# 14_Clocks_1.net
KiCad netlist of a schematic drawn in Altium Designer
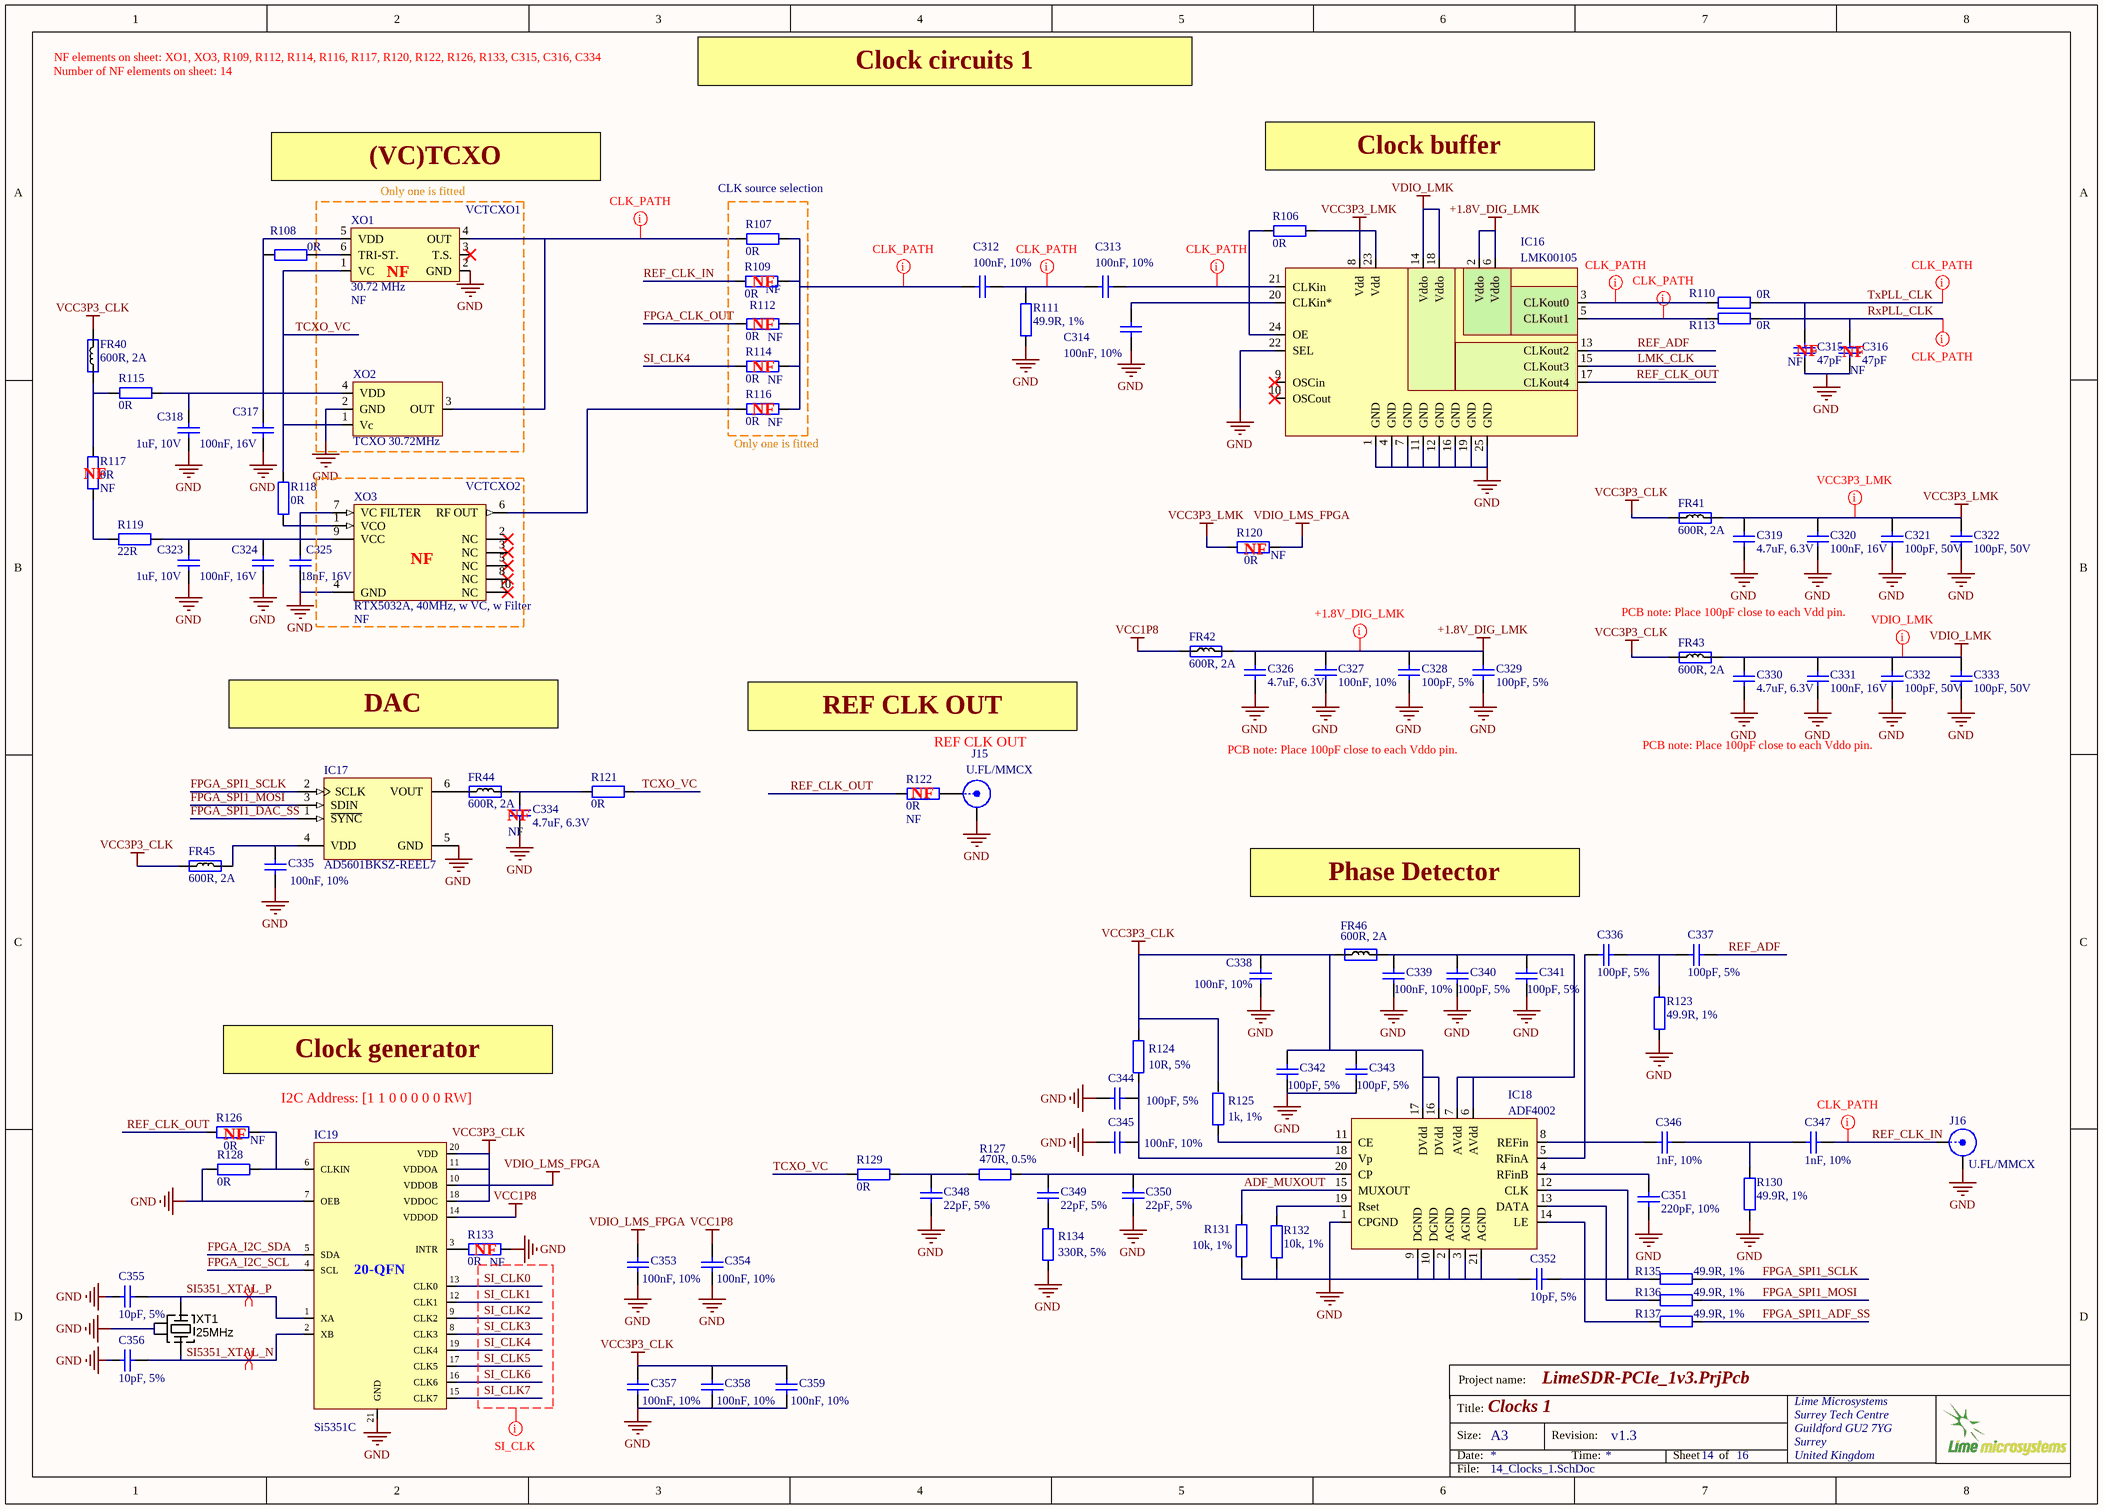
[diagram p0: 14_Clocks_1.SchDoc]

(export (version "E")
  (design (tool "Eeschema 10.0.6"))
  (components
    (comp (ref "C312")
      (value "100nF, 10%")
      (footprint "CAP0402")
      (fields
        (field (name "MANUFACTURER") "Murata Electronics")
        (field (name "TOLERANCE") "10 %")
        (field (name "MANUFACTURER PART NUMBER") "GRM155R71C104KA88D")
      )
      (libsource (lib "LimeMicroAltiumLib_schLib") (part "Cap_0402"))
    )
    (comp (ref "C313")
      (value "100nF, 10%")
      (footprint "CAP0402")
      (fields
        (field (name "MANUFACTURER") "Murata Electronics")
        (field (name "TOLERANCE") "10 %")
        (field (name "MANUFACTURER PART NUMBER") "GRM155R71C104KA88D")
      )
      (libsource (lib "LimeMicroAltiumLib_schLib") (part "Cap_0402"))
    )
    (comp (ref "C314")
      (value "100nF, 10%")
      (footprint "CAP0402")
      (fields
        (field (name "MANUFACTURER") "Murata Electronics")
        (field (name "TOLERANCE") "10 %")
        (field (name "MANUFACTURER PART NUMBER") "GRM155R71C104KA88D")
      )
      (libsource (lib "LimeMicroAltiumLib_schLib") (part "Cap_0402"))
    )
    (comp (ref "C315")
      (value "47pF")
      (footprint "CAP0402")
      (fields
        (field (name "TOLERANCE") "±1%")
        (field (name "MANUFACTURER") "TDK Corporation")
        (field (name "ASSEMBLY INFO") "NF")
      )
      (libsource (lib "LimeMicroAltiumLib_schLib") (part "Cap_0402"))
    )
    (comp (ref "C316")
      (value "47pF")
      (footprint "CAP0402")
      (fields
        (field (name "TOLERANCE") "±1%")
        (field (name "MANUFACTURER") "TDK Corporation")
        (field (name "ASSEMBLY INFO") "NF")
      )
      (libsource (lib "LimeMicroAltiumLib_schLib") (part "Cap_0402"))
    )
    (comp (ref "C317")
      (value "100nF, 16V")
      (footprint "CAP0402")
      (fields
        (field (name "MANUFACTURER") "Murata Electronics")
        (field (name "TOLERANCE") "10 %")
        (field (name "MANUFACTURER PART NUMBER") "GRM155R71C104KA88D")
      )
      (libsource (lib "LimeMicroAltiumLib_schLib") (part "Cap_0402"))
    )
    (comp (ref "C318")
      (value "1uF, 10V")
      (footprint "CAP0402")
      (fields (field (name "MANUFACTURER") "TDK"))
      (libsource (lib "LimeMicroAltiumLib_schLib") (part "Cap_0402"))
    )
    (comp (ref "C319")
      (value "4.7uF, 6.3V")
      (footprint "CAP0402")
      (fields
        (field (name "MANUFACTURER") "Murata Electronics North America")
        (field (name "TOLERANCE") "±20%")
      )
      (libsource (lib "LimeMicroAltiumLib_schLib") (part "Cap_0402"))
    )
    (comp (ref "C320")
      (value "100nF, 16V")
      (footprint "CAP0402")
      (fields
        (field (name "MANUFACTURER") "Murata Electronics")
        (field (name "TOLERANCE") "10 %")
        (field (name "MANUFACTURER PART NUMBER") "GRM155R71C104KA88D")
      )
      (libsource (lib "LimeMicroAltiumLib_schLib") (part "Cap_0402"))
    )
    (comp (ref "C321")
      (value "100pF, 50V")
      (footprint "CAP0402")
      (fields (field (name "MANUFACTURER") "Yageo") (field (name "TOLERANCE") "±5%"))
      (libsource (lib "LimeMicroAltiumLib_schLib") (part "Cap_0402"))
    )
    (comp (ref "C322")
      (value "100pF, 50V")
      (footprint "CAP0402")
      (fields (field (name "MANUFACTURER") "Yageo") (field (name "TOLERANCE") "±5%"))
      (libsource (lib "LimeMicroAltiumLib_schLib") (part "Cap_0402"))
    )
    (comp (ref "C323")
      (value "1uF, 10V")
      (footprint "CAP0402")
      (fields (field (name "MANUFACTURER") "TDK"))
      (libsource (lib "LimeMicroAltiumLib_schLib") (part "Cap_0402"))
    )
    (comp (ref "C324")
      (value "100nF, 16V")
      (footprint "CAP0402")
      (fields
        (field (name "MANUFACTURER") "Murata Electronics")
        (field (name "TOLERANCE") "10 %")
        (field (name "MANUFACTURER PART NUMBER") "GRM155R71C104KA88D")
      )
      (libsource (lib "LimeMicroAltiumLib_schLib") (part "Cap_0402"))
    )
    (comp (ref "C325")
      (value "18nF, 16V")
      (footprint "CAP0402")
      (fields (field (name "MANUFACTURER") "Yageo") (field (name "TOLERANCE") "±10%"))
      (libsource (lib "LimeMicroAltiumLib_schLib") (part "Cap_0402"))
    )
    (comp (ref "C326")
      (value "4.7uF, 6.3V")
      (footprint "CAP0402")
      (fields
        (field (name "MANUFACTURER") "Murata Electronics North America")
        (field (name "TOLERANCE") "±20%")
      )
      (libsource (lib "LimeMicroAltiumLib_schLib") (part "Cap_0402"))
    )
    (comp (ref "C327")
      (value "100nF, 10%")
      (footprint "CAP0402")
      (fields
        (field (name "MANUFACTURER") "Murata Electronics")
        (field (name "TOLERANCE") "10 %")
        (field (name "MANUFACTURER PART NUMBER") "GRM155R71C104KA88D")
      )
      (libsource (lib "LimeMicroAltiumLib_schLib") (part "Cap_0402"))
    )
    (comp (ref "C328")
      (value "100pF, 5%")
      (footprint "CAP0402")
      (fields (field (name "MANUFACTURER") "Yageo") (field (name "TOLERANCE") "±5%"))
      (libsource (lib "LimeMicroAltiumLib_schLib") (part "Cap_0402"))
    )
    (comp (ref "C329")
      (value "100pF, 5%")
      (footprint "CAP0402")
      (fields (field (name "MANUFACTURER") "Yageo") (field (name "TOLERANCE") "±5%"))
      (libsource (lib "LimeMicroAltiumLib_schLib") (part "Cap_0402"))
    )
    (comp (ref "C330")
      (value "4.7uF, 6.3V")
      (footprint "CAP0402")
      (fields
        (field (name "MANUFACTURER") "Murata Electronics North America")
        (field (name "TOLERANCE") "±20%")
      )
      (libsource (lib "LimeMicroAltiumLib_schLib") (part "Cap_0402"))
    )
    (comp (ref "C331")
      (value "100nF, 16V")
      (footprint "CAP0402")
      (fields
        (field (name "MANUFACTURER") "Murata Electronics")
        (field (name "TOLERANCE") "10 %")
        (field (name "MANUFACTURER PART NUMBER") "GRM155R71C104KA88D")
      )
      (libsource (lib "LimeMicroAltiumLib_schLib") (part "Cap_0402"))
    )
    (comp (ref "C332")
      (value "100pF, 50V")
      (footprint "CAP0402")
      (fields (field (name "MANUFACTURER") "Yageo") (field (name "TOLERANCE") "±5%"))
      (libsource (lib "LimeMicroAltiumLib_schLib") (part "Cap_0402"))
    )
    (comp (ref "C333")
      (value "100pF, 50V")
      (footprint "CAP0402")
      (fields (field (name "MANUFACTURER") "Yageo") (field (name "TOLERANCE") "±5%"))
      (libsource (lib "LimeMicroAltiumLib_schLib") (part "Cap_0402"))
    )
    (comp (ref "C334")
      (value "4.7uF, 6.3V")
      (footprint "CAP0402")
      (fields
        (field (name "ASSEMBLY INFO") "NF")
        (field (name "MANUFACTURER") "Murata Electronics North America")
        (field (name "TOLERANCE") "±20%")
      )
      (libsource (lib "LimeMicroAltiumLib_schLib") (part "Cap_0402"))
    )
    (comp (ref "C335")
      (value "100nF, 10%")
      (footprint "CAP0402")
      (fields
        (field (name "TOLERANCE") "10 %")
        (field (name "MANUFACTURER") "Murata Electronics")
        (field (name "MANUFACTURER PART NUMBER") "GRM155R71C104KA88D")
      )
      (libsource (lib "LimeFPGAboard_schLib") (part "Cap_0603"))
    )
    (comp (ref "C336")
      (value "100pF, 5%")
      (footprint "CAP0402")
      (fields (field (name "MANUFACTURER") "Yageo") (field (name "TOLERANCE") "±5%"))
      (libsource (lib "LimeMicroAltiumLib_schLib") (part "Cap_0402"))
    )
    (comp (ref "C337")
      (value "100pF, 5%")
      (footprint "CAP0402")
      (fields (field (name "MANUFACTURER") "Yageo") (field (name "TOLERANCE") "±5%"))
      (libsource (lib "LimeMicroAltiumLib_schLib") (part "Cap_0402"))
    )
    (comp (ref "C338")
      (value "100nF, 10%")
      (footprint "CAP0402")
      (fields
        (field (name "MANUFACTURER") "Murata Electronics")
        (field (name "TOLERANCE") "10 %")
        (field (name "MANUFACTURER PART NUMBER") "GRM155R71C104KA88D")
      )
      (libsource (lib "LimeMicroAltiumLib_schLib") (part "Cap_0402"))
    )
    (comp (ref "C339")
      (value "100nF, 10%")
      (footprint "CAP0402")
      (fields
        (field (name "MANUFACTURER") "Murata Electronics")
        (field (name "TOLERANCE") "10 %")
        (field (name "MANUFACTURER PART NUMBER") "GRM155R71C104KA88D")
      )
      (libsource (lib "LimeMicroAltiumLib_schLib") (part "Cap_0402"))
    )
    (comp (ref "C340")
      (value "100pF, 5%")
      (footprint "CAP0402")
      (fields (field (name "MANUFACTURER") "Yageo") (field (name "TOLERANCE") "±5%"))
      (libsource (lib "LimeMicroAltiumLib_schLib") (part "Cap_0402"))
    )
    (comp (ref "C341")
      (value "100pF, 5%")
      (footprint "CAP0402")
      (fields (field (name "MANUFACTURER") "Yageo") (field (name "TOLERANCE") "±5%"))
      (libsource (lib "LimeMicroAltiumLib_schLib") (part "Cap_0402"))
    )
    (comp (ref "C342")
      (value "100pF, 5%")
      (footprint "CAP0402")
      (fields (field (name "MANUFACTURER") "Yageo") (field (name "TOLERANCE") "±5%"))
      (libsource (lib "LimeMicroAltiumLib_schLib") (part "Cap_0402"))
    )
    (comp (ref "C343")
      (value "100pF, 5%")
      (footprint "CAP0402")
      (fields (field (name "MANUFACTURER") "Yageo") (field (name "TOLERANCE") "±5%"))
      (libsource (lib "LimeMicroAltiumLib_schLib") (part "Cap_0402"))
    )
    (comp (ref "C344")
      (value "100pF, 5%")
      (footprint "CAP0402")
      (fields (field (name "MANUFACTURER") "Yageo") (field (name "TOLERANCE") "±5%"))
      (libsource (lib "LimeMicroAltiumLib_schLib") (part "Cap_0402"))
    )
    (comp (ref "C345")
      (value "100nF, 10%")
      (footprint "CAP0402")
      (fields
        (field (name "MANUFACTURER") "Murata Electronics")
        (field (name "TOLERANCE") "10 %")
        (field (name "MANUFACTURER PART NUMBER") "GRM155R71C104KA88D")
      )
      (libsource (lib "LimeMicroAltiumLib_schLib") (part "Cap_0402"))
    )
    (comp (ref "C346")
      (value "1nF, 10%")
      (footprint "CAP0402")
      (fields (field (name "TOLERANCE") "10 %") (field (name "MANUFACTURER") "Murata Electronics"))
      (libsource (lib "LimeMicroAltiumLib_schLib") (part "Cap_0402"))
    )
    (comp (ref "C347")
      (value "1nF, 10%")
      (footprint "CAP0402")
      (fields (field (name "TOLERANCE") "10 %") (field (name "MANUFACTURER") "Murata Electronics"))
      (libsource (lib "LimeMicroAltiumLib_schLib") (part "Cap_0402"))
    )
    (comp (ref "C348")
      (value "22pF, 5%")
      (footprint "CAP0402")
      (fields (field (name "TOLERANCE") "±5%") (field (name "MANUFACTURER") "Yageo"))
      (libsource (lib "LimeMicroAltiumLib_schLib") (part "Cap_0402"))
    )
    (comp (ref "C349")
      (value "22pF, 5%")
      (footprint "CAP0402")
      (fields (field (name "TOLERANCE") "±5%") (field (name "MANUFACTURER") "Yageo"))
      (libsource (lib "LimeMicroAltiumLib_schLib") (part "Cap_0402"))
    )
    (comp (ref "C350")
      (value "22pF, 5%")
      (footprint "CAP0402")
      (fields (field (name "TOLERANCE") "±5%") (field (name "MANUFACTURER") "Yageo"))
      (libsource (lib "LimeMicroAltiumLib_schLib") (part "Cap_0402"))
    )
    (comp (ref "C351")
      (value "220pF, 10%")
      (footprint "CAP0402")
      (fields (field (name "MANUFACTURER") "Yageo") (field (name "TOLERANCE") "±10%"))
      (libsource (lib "LimeMicroAltiumLib_schLib") (part "Cap_0402"))
    )
    (comp (ref "C352")
      (value "10pF, 5%")
      (footprint "CAP0402")
      (fields (field (name "MANUFACTURER") "AVX"))
      (libsource (lib "LimeMicroAltiumLib_schLib") (part "Cap_0402"))
    )
    (comp (ref "C353")
      (value "100nF, 10%")
      (footprint "CAP0402")
      (fields
        (field (name "TOLERANCE") "10 %")
        (field (name "MANUFACTURER") "Murata Electronics")
        (field (name "MANUFACTURER PART NUMBER") "GRM155R71C104KA88D")
      )
      (libsource (lib "LimeFPGAboard_schLib") (part "Cap_0603"))
    )
    (comp (ref "C354")
      (value "100nF, 10%")
      (footprint "CAP0402")
      (fields
        (field (name "TOLERANCE") "10 %")
        (field (name "MANUFACTURER") "Murata Electronics")
        (field (name "MANUFACTURER PART NUMBER") "GRM155R71C104KA88D")
      )
      (libsource (lib "LimeFPGAboard_schLib") (part "Cap_0603"))
    )
    (comp (ref "C355")
      (value "10pF, 5%")
      (footprint "CAP0402")
      (fields (field (name "MANUFACTURER") "AVX"))
      (libsource (lib "LimeFPGAboard_schLib") (part "Cap_0402"))
    )
    (comp (ref "C356")
      (value "10pF, 5%")
      (footprint "CAP0402")
      (fields (field (name "MANUFACTURER") "AVX"))
      (libsource (lib "LimeFPGAboard_schLib") (part "Cap_0402"))
    )
    (comp (ref "C357")
      (value "100nF, 10%")
      (footprint "CAP0402")
      (fields
        (field (name "TOLERANCE") "10 %")
        (field (name "MANUFACTURER") "Murata Electronics")
        (field (name "MANUFACTURER PART NUMBER") "GRM155R71C104KA88D")
      )
      (libsource (lib "LimeFPGAboard_schLib") (part "Cap_0603"))
    )
    (comp (ref "C358")
      (value "100nF, 10%")
      (footprint "CAP0402")
      (fields
        (field (name "TOLERANCE") "10 %")
        (field (name "MANUFACTURER") "Murata Electronics")
        (field (name "MANUFACTURER PART NUMBER") "GRM155R71C104KA88D")
      )
      (libsource (lib "LimeFPGAboard_schLib") (part "Cap_0603"))
    )
    (comp (ref "C359")
      (value "100nF, 10%")
      (footprint "CAP0402")
      (fields
        (field (name "TOLERANCE") "10 %")
        (field (name "MANUFACTURER") "Murata Electronics")
        (field (name "MANUFACTURER PART NUMBER") "GRM155R71C104KA88D")
      )
      (libsource (lib "LimeFPGAboard_schLib") (part "Cap_0603"))
    )
    (comp (ref "FR40")
      (value "600R, 2A")
      (footprint "RES0805")
      (fields (field (name "MANUFACTURER") "TDK Corporation"))
      (libsource (lib "LimeFPGAboard_schLib") (part "Ferrite"))
    )
    (comp (ref "FR41")
      (value "600R, 2A")
      (footprint "RES0805")
      (fields (field (name "MANUFACTURER") "TDK Corporation"))
      (libsource (lib "LimeMicroAltiumLib_schLib") (part "Ferrite"))
    )
    (comp (ref "FR42")
      (value "600R, 2A")
      (footprint "RES0805")
      (fields (field (name "MANUFACTURER") "TDK Corporation"))
      (libsource (lib "LimeMicroAltiumLib_schLib") (part "Ferrite"))
    )
    (comp (ref "FR43")
      (value "600R, 2A")
      (footprint "RES0805")
      (fields (field (name "MANUFACTURER") "TDK Corporation"))
      (libsource (lib "LimeMicroAltiumLib_schLib") (part "Ferrite"))
    )
    (comp (ref "FR44")
      (value "600R, 2A")
      (footprint "RES0805")
      (fields (field (name "MANUFACTURER") "TDK Corporation"))
      (libsource (lib "LimeMicroAltiumLib_schLib") (part "Ferrite"))
    )
    (comp (ref "FR45")
      (value "600R, 2A")
      (footprint "RES0805")
      (fields (field (name "MANUFACTURER") "TDK Corporation"))
      (libsource (lib "LimeMicroAltiumLib_schLib") (part "Ferrite"))
    )
    (comp (ref "FR46")
      (value "600R, 2A")
      (footprint "RES0805")
      (fields (field (name "MANUFACTURER") "TDK Corporation"))
      (libsource (lib "LimeMicroAltiumLib_schLib") (part "Ferrite"))
    )
    (comp (ref "IC16")
      (value "LMK00105")
      (footprint "LMK00105SQ")
      (fields (field (name "MANUFACTURER") "Texas Instruments"))
      (libsource (lib "LimeMicroAltiumLib_schLib") (part "LMK00105"))
    )
    (comp (ref "IC17")
      (value "AD5601BKSZ-REEL7")
      (footprint "AD5601_SOT23-6")
      (fields (field (name "GENERIC PART NUMBER") "AD5601") (field (name "MANUFACTURER") "Analog Devices"))
      (libsource (lib "LimeMicroAltiumLib_schLib") (part "AD5601BKSZ-REEL7"))
    )
    (comp (ref "IC18")
      (value "ADF4002")
      (footprint "ADF4002")
      (fields (field (name "MANUFACTURER") "Analog Devices Inc"))
      (libsource (lib "LimeMicroAltiumLib_schLib") (part "ADF4002"))
    )
    (comp (ref "IC19")
      (value "Si5351C")
      (footprint "Si5351C_20QFN")
      (fields (field (name "MANUFACTURER") "Silicon Labs"))
      (libsource (lib "LimeFPGAboard_schLib") (part "Si5351C"))
    )
    (comp (ref "J15")
      (value "U.FL/MMCX")
      (footprint "MMCX_UFL_conn_u")
      (fields (field (name "MANUFACTURER") "Molex, LLC"))
      (libsource (lib "LimeMicroAltiumLib_schLib") (part "RF_IF_connector"))
    )
    (comp (ref "J16")
      (value "U.FL/MMCX")
      (footprint "MMCX_UFL_conn_u")
      (fields (field (name "MANUFACTURER") "Molex, LLC"))
      (libsource (lib "LimeMicroAltiumLib_schLib") (part "RF_IF_connector"))
    )
    (comp (ref "R106")
      (value "0R")
      (footprint "RES0402")
      (fields (field (name "MANUFACTURER") "Yageo") (field (name "TOLERANCE") "Jumper"))
      (libsource (lib "LimeMicroAltiumLib_schLib") (part "Res_0402"))
    )
    (comp (ref "R107")
      (value "0R")
      (footprint "RES0402_v2")
      (fields (field (name "MANUFACTURER") "Yageo") (field (name "TOLERANCE") "Jumper"))
      (libsource (lib "LimeMicroAltiumLib_schLib") (part "Res_0402"))
    )
    (comp (ref "R108")
      (value "0R")
      (footprint "RES0402")
      (fields (field (name "MANUFACTURER") "Yageo") (field (name "TOLERANCE") "Jumper"))
      (libsource (lib "LimeMicroAltiumLib_schLib") (part "Res_0402"))
    )
    (comp (ref "R109")
      (value "0R")
      (footprint "RES0402_v2")
      (fields
        (field (name "ASSEMBLY INFO") "NF")
        (field (name "MANUFACTURER") "Yageo")
        (field (name "TOLERANCE") "Jumper")
      )
      (libsource (lib "LimeMicroAltiumLib_schLib") (part "Res_0402"))
    )
    (comp (ref "R110")
      (value "0R")
      (footprint "RES0402")
      (fields (field (name "MANUFACTURER") "Yageo") (field (name "TOLERANCE") "Jumper"))
      (libsource (lib "LimeMicroAltiumLib_schLib") (part "Res_0402"))
    )
    (comp (ref "R111")
      (value "49.9R, 1%")
      (footprint "RES0402")
      (fields
        (field (name "TOLERANCE") "±1%")
        (field (name "MANUFACTURER") "Samsung Electro-Mechanics America, Inc.")
        (field (name "MANUFACTURER PART NUMBER") "RC1005F49R9CS")
      )
      (libsource (lib "LimeMicroAltiumLib_schLib") (part "Res_0402"))
    )
    (comp (ref "R112")
      (value "0R")
      (footprint "RES0402_v2")
      (fields
        (field (name "ASSEMBLY INFO") "NF")
        (field (name "MANUFACTURER") "Yageo")
        (field (name "TOLERANCE") "Jumper")
      )
      (libsource (lib "LimeMicroAltiumLib_schLib") (part "Res_0402"))
    )
    (comp (ref "R113")
      (value "0R")
      (footprint "RES0402")
      (fields (field (name "MANUFACTURER") "Yageo") (field (name "TOLERANCE") "Jumper"))
      (libsource (lib "LimeMicroAltiumLib_schLib") (part "Res_0402"))
    )
    (comp (ref "R114")
      (value "0R")
      (footprint "RES0402_v2")
      (fields
        (field (name "ASSEMBLY INFO") "NF")
        (field (name "MANUFACTURER") "Yageo")
        (field (name "TOLERANCE") "Jumper")
      )
      (libsource (lib "LimeMicroAltiumLib_schLib") (part "Res_0402"))
    )
    (comp (ref "R115")
      (value "0R")
      (footprint "RES0402")
      (fields (field (name "MANUFACTURER") "Yageo") (field (name "TOLERANCE") "Jumper"))
      (libsource (lib "LimeMicroAltiumLib_schLib") (part "Res_0402"))
    )
    (comp (ref "R116")
      (value "0R")
      (footprint "RES0402_v2")
      (fields
        (field (name "ASSEMBLY INFO") "NF")
        (field (name "MANUFACTURER") "Yageo")
        (field (name "TOLERANCE") "Jumper")
      )
      (libsource (lib "LimeMicroAltiumLib_schLib") (part "Res_0402"))
    )
    (comp (ref "R117")
      (value "0R")
      (footprint "RES0402")
      (fields
        (field (name "ASSEMBLY INFO") "NF")
        (field (name "MANUFACTURER") "Yageo")
        (field (name "TOLERANCE") "Jumper")
      )
      (libsource (lib "LimeMicroAltiumLib_schLib") (part "Res_0402"))
    )
    (comp (ref "R118")
      (value "0R")
      (footprint "RES0402")
      (fields (field (name "MANUFACTURER") "Yageo") (field (name "TOLERANCE") "Jumper"))
      (libsource (lib "LimeMicroAltiumLib_schLib") (part "Res_0402"))
    )
    (comp (ref "R119")
      (value "22R")
      (footprint "RES0402")
      (fields (field (name "TOLERANCE") "±1%") (field (name "MANUFACTURER") "Yageo"))
      (libsource (lib "LimeFPGAboard_schLib") (part "Res_0402"))
    )
    (comp (ref "R120")
      (value "0R")
      (footprint "RES0402")
      (fields
        (field (name "ASSEMBLY INFO") "NF")
        (field (name "MANUFACTURER") "Yageo")
        (field (name "TOLERANCE") "Jumper")
      )
      (libsource (lib "LimeMicroAltiumLib_schLib") (part "Res_0402"))
    )
    (comp (ref "R121")
      (value "0R")
      (footprint "RES0402")
      (fields (field (name "MANUFACTURER") "Yageo") (field (name "TOLERANCE") "Jumper"))
      (libsource (lib "LimeMicroAltiumLib_schLib") (part "Res_0402"))
    )
    (comp (ref "R122")
      (value "0R")
      (footprint "RES0402")
      (fields
        (field (name "ASSEMBLY INFO") "NF")
        (field (name "MANUFACTURER") "Yageo")
        (field (name "TOLERANCE") "Jumper")
      )
      (libsource (lib "LimeMicroAltiumLib_schLib") (part "Res_0402"))
    )
    (comp (ref "R123")
      (value "49.9R, 1%")
      (footprint "RES0402")
      (fields
        (field (name "TOLERANCE") "±1%")
        (field (name "MANUFACTURER") "Samsung Electro-Mechanics America, Inc.")
        (field (name "MANUFACTURER PART NUMBER") "RC1005F49R9CS")
      )
      (libsource (lib "LimeMicroAltiumLib_schLib") (part "Res_0402"))
    )
    (comp (ref "R124")
      (value "10R, 5%")
      (footprint "RES0402")
      (fields (field (name "TOLERANCE") "±5%") (field (name "MANUFACTURER") "Yageo"))
      (libsource (lib "LimeMicroAltiumLib_schLib") (part "Res_0402"))
    )
    (comp (ref "R125")
      (value "1k, 1%")
      (footprint "RES0402")
      (fields (field (name "MANUFACTURER") "Stackpole Electronics Inc") (field (name "TOLERANCE") "±1%"))
      (libsource (lib "LimeMicroAltiumLib_schLib") (part "Res_0402"))
    )
    (comp (ref "R126")
      (value "0R")
      (footprint "RES0402")
      (fields
        (field (name "ASSEMBLY INFO") "NF")
        (field (name "MANUFACTURER") "Yageo")
        (field (name "TOLERANCE") "Jumper")
      )
      (libsource (lib "LimeMicroAltiumLib_schLib") (part "Res_0402"))
    )
    (comp (ref "R127")
      (value "470R, 0.5%")
      (footprint "RES0402")
      (fields
        (field (name "TOLERANCE") "±0.5%")
        (field (name "MANUFACTURER") "Panasonic Electronic Components")
      )
      (libsource (lib "LimeMicroAltiumLib_schLib") (part "Res_0402"))
    )
    (comp (ref "R128")
      (value "0R")
      (footprint "RES0402")
      (fields (field (name "MANUFACTURER") "Yageo") (field (name "TOLERANCE") "Jumper"))
      (libsource (lib "LimeMicroAltiumLib_schLib") (part "Res_0402"))
    )
    (comp (ref "R129")
      (value "0R")
      (footprint "RES0402")
      (fields (field (name "MANUFACTURER") "Yageo") (field (name "TOLERANCE") "Jumper"))
      (libsource (lib "LimeMicroAltiumLib_schLib") (part "Res_0402"))
    )
    (comp (ref "R130")
      (value "49.9R, 1%")
      (footprint "RES0402")
      (fields
        (field (name "TOLERANCE") "±1%")
        (field (name "MANUFACTURER") "Samsung Electro-Mechanics America, Inc.")
        (field (name "MANUFACTURER PART NUMBER") "RC1005F49R9CS")
      )
      (libsource (lib "LimeMicroAltiumLib_schLib") (part "Res_0402"))
    )
    (comp (ref "R131")
      (value "10k, 1%")
      (footprint "RES0402")
      (fields (field (name "MANUFACTURER") "Yageo") (field (name "TOLERANCE") "±1%"))
      (libsource (lib "LimeMicroAltiumLib_schLib") (part "Res_0402"))
    )
    (comp (ref "R132")
      (value "10k, 1%")
      (footprint "RES0402")
      (fields (field (name "MANUFACTURER") "Yageo") (field (name "TOLERANCE") "±1%"))
      (libsource (lib "LimeMicroAltiumLib_schLib") (part "Res_0402"))
    )
    (comp (ref "R133")
      (value "0R")
      (footprint "RES0402")
      (fields
        (field (name "ASSEMBLY INFO") "NF")
        (field (name "MANUFACTURER") "Yageo")
        (field (name "TOLERANCE") "Jumper")
      )
      (libsource (lib "LimeMicroAltiumLib_schLib") (part "Res_0402"))
    )
    (comp (ref "R134")
      (value "330R, 5%")
      (footprint "RES0402")
      (fields (field (name "MANUFACTURER") "Yageo") (field (name "TOLERANCE") "±5%"))
      (libsource (lib "LimeMicroAltiumLib_schLib") (part "Res_0402"))
    )
    (comp (ref "R135")
      (value "49.9R, 1%")
      (footprint "RES0402")
      (fields
        (field (name "TOLERANCE") "±1%")
        (field (name "MANUFACTURER") "Samsung Electro-Mechanics America, Inc.")
        (field (name "MANUFACTURER PART NUMBER") "RC1005F49R9CS")
      )
      (libsource (lib "LimeMicroAltiumLib_schLib") (part "Res_0402"))
    )
    (comp (ref "R136")
      (value "49.9R, 1%")
      (footprint "RES0402")
      (fields
        (field (name "TOLERANCE") "±1%")
        (field (name "MANUFACTURER") "Samsung Electro-Mechanics America, Inc.")
        (field (name "MANUFACTURER PART NUMBER") "RC1005F49R9CS")
      )
      (libsource (lib "LimeMicroAltiumLib_schLib") (part "Res_0402"))
    )
    (comp (ref "R137")
      (value "49.9R, 1%")
      (footprint "RES0402")
      (fields
        (field (name "TOLERANCE") "±1%")
        (field (name "MANUFACTURER") "Samsung Electro-Mechanics America, Inc.")
        (field (name "MANUFACTURER PART NUMBER") "RC1005F49R9CS")
      )
      (libsource (lib "LimeMicroAltiumLib_schLib") (part "Res_0402"))
    )
    (comp (ref "XO1")
      (value "30.72 MHz")
      (footprint "RAKON_RPT7050A")
      (fields (field (name "ASSEMBLY INFO") "NF") (field (name "MANUFACTURER") "Rakon"))
      (libsource (lib "LimeMicroAltiumLib_schLib") (part "RPT7050A"))
    )
    (comp (ref "XO2")
      (value "TCXO 30.72MHz")
      (footprint "RAKON_TXCO")
      (fields (field (name "MANUFACTURER") "Rakon"))
      (libsource (lib "LimeMicroAltiumLib_schLib") (part "TXCO"))
    )
    (comp (ref "XO3")
      (value "RTX5032A, 40MHz, w VC, w Filter")
      (footprint "RAKON_RTX5032A")
      (fields (field (name "ASSEMBLY INFO") "NF") (field (name "MANUFACTURER") "Rakon"))
      (libsource (lib "LimeMicroAltiumLib_schLib") (part "Rakon_RTX5032A"))
    )
    (comp (ref "XT1")
      (value "25MHz")
      (footprint "CRYSTAL_4-LCC")
      (description "Oscillator Crystal 25 MHz")
      (fields (field (name "MANUFACTURER") "ABRACON"))
      (libsource (lib "LimeFPGAboard_schLib") (part "CRYSTAL_19M2"))
    )
  )
  (nets
    (net (code "1") (name "+1.8V_DIG_LMK") (class "Default")
      (node (ref "C326") (pin "2") (pinfunction "2_2") (pintype "passive"))
      (node (ref "C327") (pin "2") (pinfunction "2_2") (pintype "passive"))
      (node (ref "C328") (pin "2") (pinfunction "2_2") (pintype "passive"))
      (node (ref "C329") (pin "2") (pinfunction "2_2") (pintype "passive"))
      (node (ref "FR42") (pin "2") (pinfunction "2_2") (pintype "passive"))
      (node (ref "IC16") (pin "2") (pinfunction "Vddo_2") (pintype "passive"))
      (node (ref "IC16") (pin "6") (pinfunction "Vddo_6") (pintype "passive"))
    )
    (net (code "2") (name "/ADF_MUXOUT") (class "Default")
      (node (ref "IC18") (pin "15") (pinfunction "MUXOUT_15") (pintype "passive"))
      (node (ref "R131") (pin "1") (pinfunction "1_1") (pintype "passive"))
    )
    (net (code "3") (name "/FPGA_CLK_OUT") (class "Default")
      (node (ref "R112") (pin "2") (pinfunction "2_2") (pintype "passive"))
    )
    (net (code "4") (name "/FPGA_I2C_SCL") (class "Default")
      (node (ref "IC19") (pin "4") (pinfunction "SCL_4") (pintype "passive"))
    )
    (net (code "5") (name "/FPGA_I2C_SDA") (class "Default")
      (node (ref "IC19") (pin "5") (pinfunction "SDA_5") (pintype "passive"))
    )
    (net (code "6") (name "/FPGA_SPI1_ADF_SS") (class "Default")
      (node (ref "R137") (pin "1") (pinfunction "1_1") (pintype "passive"))
    )
    (net (code "7") (name "/FPGA_SPI1_DAC_SS") (class "Default")
      (node (ref "IC17") (pin "1") (pinfunction "~{SYNC}_1") (pintype "input"))
    )
    (net (code "8") (name "/FPGA_SPI1_MOSI") (class "Default")
      (node (ref "IC17") (pin "3") (pinfunction "SDIN_3") (pintype "input"))
      (node (ref "R136") (pin "1") (pinfunction "1_1") (pintype "passive"))
    )
    (net (code "9") (name "/FPGA_SPI1_SCLK") (class "Default")
      (node (ref "IC17") (pin "2") (pinfunction "SCLK_2") (pintype "input"))
      (node (ref "R135") (pin "1") (pinfunction "1_1") (pintype "passive"))
    )
    (net (code "10") (name "/LMK_CLK") (class "Default")
      (node (ref "IC16") (pin "15") (pinfunction "CLKout3_15") (pintype "passive"))
    )
    (net (code "11") (name "/REF_ADF") (class "Default")
      (node (ref "C337") (pin "2") (pinfunction "2_2") (pintype "passive"))
      (node (ref "IC16") (pin "13") (pinfunction "CLKout2_13") (pintype "passive"))
    )
    (net (code "12") (name "/REF_CLK_IN") (class "Default")
      (node (ref "C347") (pin "1") (pinfunction "1_1") (pintype "passive"))
      (node (ref "J16") (pin "1") (pinfunction "X_1") (pintype "passive"))
      (node (ref "R109") (pin "1") (pinfunction "1_1") (pintype "passive"))
    )
    (net (code "13") (name "/REF_CLK_OUT") (class "Default")
      (node (ref "IC16") (pin "17") (pinfunction "CLKout4_17") (pintype "passive"))
      (node (ref "R122") (pin "2") (pinfunction "2_2") (pintype "passive"))
      (node (ref "R126") (pin "1") (pinfunction "1_1") (pintype "passive"))
    )
    (net (code "14") (name "/RxPLL_CLK") (class "Default")
      (node (ref "C316") (pin "2") (pinfunction "2_2") (pintype "passive"))
      (node (ref "R113") (pin "1") (pinfunction "1_1") (pintype "passive"))
    )
    (net (code "15") (name "/SI5351_XTAL_N") (class "Default")
      (node (ref "C356") (pin "2") (pinfunction "2_2") (pintype "passive"))
      (node (ref "IC19") (pin "2") (pinfunction "XB_2") (pintype "passive"))
      (node (ref "XT1") (pin "3") (pinfunction "X_3") (pintype "passive"))
    )
    (net (code "16") (name "/SI5351_XTAL_P") (class "Default")
      (node (ref "C355") (pin "2") (pinfunction "2_2") (pintype "passive"))
      (node (ref "IC19") (pin "1") (pinfunction "XA_1") (pintype "passive"))
      (node (ref "XT1") (pin "1") (pinfunction "X_1") (pintype "passive"))
    )
    (net (code "17") (name "/SI_CLK0") (class "Default")
      (node (ref "IC19") (pin "13") (pinfunction "CLK0_13") (pintype "passive"))
    )
    (net (code "18") (name "/SI_CLK1") (class "Default")
      (node (ref "IC19") (pin "12") (pinfunction "CLK1_12") (pintype "passive"))
    )
    (net (code "19") (name "/SI_CLK2") (class "Default")
      (node (ref "IC19") (pin "9") (pinfunction "CLK2_9") (pintype "passive"))
    )
    (net (code "20") (name "/SI_CLK3") (class "Default")
      (node (ref "IC19") (pin "8") (pinfunction "CLK3_8") (pintype "passive"))
    )
    (net (code "21") (name "/SI_CLK4") (class "Default")
      (node (ref "IC19") (pin "19") (pinfunction "CLK4_19") (pintype "passive"))
      (node (ref "R114") (pin "2") (pinfunction "2_2") (pintype "passive"))
    )
    (net (code "22") (name "/SI_CLK5") (class "Default")
      (node (ref "IC19") (pin "17") (pinfunction "CLK5_17") (pintype "passive"))
    )
    (net (code "23") (name "/SI_CLK6") (class "Default")
      (node (ref "IC19") (pin "16") (pinfunction "CLK6_16") (pintype "passive"))
    )
    (net (code "24") (name "/SI_CLK7") (class "Default")
      (node (ref "IC19") (pin "15") (pinfunction "CLK7_15") (pintype "passive"))
    )
    (net (code "25") (name "/TCXO_VC") (class "Default")
      (node (ref "R118") (pin "1") (pinfunction "1_1") (pintype "passive"))
      (node (ref "R121") (pin "1") (pinfunction "1_1") (pintype "passive"))
      (node (ref "R129") (pin "2") (pinfunction "2_2") (pintype "passive"))
      (node (ref "XO1") (pin "1") (pinfunction "VC_1") (pintype "passive"))
      (node (ref "XO2") (pin "1") (pinfunction "Vc_1") (pintype "passive"))
    )
    (net (code "26") (name "/TxPLL_CLK") (class "Default")
      (node (ref "C315") (pin "2") (pinfunction "2_2") (pintype "passive"))
      (node (ref "R110") (pin "1") (pinfunction "1_1") (pintype "passive"))
    )
    (net (code "27") (name "GND") (class "Default")
      (node (ref "C314") (pin "1") (pinfunction "1_1") (pintype "passive"))
      (node (ref "C315") (pin "1") (pinfunction "1_1") (pintype "passive"))
      (node (ref "C316") (pin "1") (pinfunction "1_1") (pintype "passive"))
      (node (ref "C317") (pin "1") (pinfunction "1_1") (pintype "passive"))
      (node (ref "C318") (pin "1") (pinfunction "1_1") (pintype "passive"))
      (node (ref "C319") (pin "1") (pinfunction "1_1") (pintype "passive"))
      (node (ref "C320") (pin "1") (pinfunction "1_1") (pintype "passive"))
      (node (ref "C321") (pin "1") (pinfunction "1_1") (pintype "passive"))
      (node (ref "C322") (pin "1") (pinfunction "1_1") (pintype "passive"))
      (node (ref "C323") (pin "1") (pinfunction "1_1") (pintype "passive"))
      (node (ref "C324") (pin "1") (pinfunction "1_1") (pintype "passive"))
      (node (ref "C325") (pin "1") (pinfunction "1_1") (pintype "passive"))
      (node (ref "C326") (pin "1") (pinfunction "1_1") (pintype "passive"))
      (node (ref "C327") (pin "1") (pinfunction "1_1") (pintype "passive"))
      (node (ref "C328") (pin "1") (pinfunction "1_1") (pintype "passive"))
      (node (ref "C329") (pin "1") (pinfunction "1_1") (pintype "passive"))
      (node (ref "C330") (pin "1") (pinfunction "1_1") (pintype "passive"))
      (node (ref "C331") (pin "1") (pinfunction "1_1") (pintype "passive"))
      (node (ref "C332") (pin "1") (pinfunction "1_1") (pintype "passive"))
      (node (ref "C333") (pin "1") (pinfunction "1_1") (pintype "passive"))
      (node (ref "C334") (pin "1") (pinfunction "1_1") (pintype "passive"))
      (node (ref "C335") (pin "2") (pinfunction "2_2") (pintype "passive"))
      (node (ref "C338") (pin "1") (pinfunction "1_1") (pintype "passive"))
      (node (ref "C339") (pin "1") (pinfunction "1_1") (pintype "passive"))
      (node (ref "C340") (pin "2") (pinfunction "2_2") (pintype "passive"))
      (node (ref "C341") (pin "2") (pinfunction "2_2") (pintype "passive"))
      (node (ref "C342") (pin "2") (pinfunction "2_2") (pintype "passive"))
      (node (ref "C343") (pin "2") (pinfunction "2_2") (pintype "passive"))
      (node (ref "C344") (pin "1") (pinfunction "1_1") (pintype "passive"))
      (node (ref "C345") (pin "2") (pinfunction "2_2") (pintype "passive"))
      (node (ref "C348") (pin "1") (pinfunction "1_1") (pintype "passive"))
      (node (ref "C350") (pin "1") (pinfunction "1_1") (pintype "passive"))
      (node (ref "C351") (pin "2") (pinfunction "2_2") (pintype "passive"))
      (node (ref "C352") (pin "1") (pinfunction "1_1") (pintype "passive"))
      (node (ref "C353") (pin "2") (pinfunction "2_2") (pintype "passive"))
      (node (ref "C354") (pin "2") (pinfunction "2_2") (pintype "passive"))
      (node (ref "C355") (pin "1") (pinfunction "1_1") (pintype "passive"))
      (node (ref "C356") (pin "1") (pinfunction "1_1") (pintype "passive"))
      (node (ref "C357") (pin "2") (pinfunction "2_2") (pintype "passive"))
      (node (ref "C358") (pin "2") (pinfunction "2_2") (pintype "passive"))
      (node (ref "C359") (pin "2") (pinfunction "2_2") (pintype "passive"))
      (node (ref "IC16") (pin "1") (pinfunction "GND_1") (pintype "passive"))
      (node (ref "IC16") (pin "11") (pinfunction "GND_11") (pintype "passive"))
      (node (ref "IC16") (pin "12") (pinfunction "GND_12") (pintype "passive"))
      (node (ref "IC16") (pin "16") (pinfunction "GND_16") (pintype "passive"))
      (node (ref "IC16") (pin "19") (pinfunction "GND_19") (pintype "passive"))
      (node (ref "IC16") (pin "22") (pinfunction "SEL_22") (pintype "passive"))
      (node (ref "IC16") (pin "25") (pinfunction "GND_25") (pintype "passive"))
      (node (ref "IC16") (pin "4") (pinfunction "GND_4") (pintype "passive"))
      (node (ref "IC16") (pin "7") (pinfunction "GND_7") (pintype "passive"))
      (node (ref "IC17") (pin "5") (pinfunction "GND_5") (pintype "power_in"))
      (node (ref "IC18") (pin "1") (pinfunction "CPGND_1") (pintype "passive"))
      (node (ref "IC18") (pin "10") (pinfunction "DGND_10") (pintype "passive"))
      (node (ref "IC18") (pin "2") (pinfunction "AGND_2") (pintype "passive"))
      (node (ref "IC18") (pin "21") (pinfunction "AGND_21") (pintype "passive"))
      (node (ref "IC18") (pin "3") (pinfunction "AGND_3") (pintype "passive"))
      (node (ref "IC18") (pin "9") (pinfunction "DGND_9") (pintype "passive"))
      (node (ref "IC19") (pin "21") (pinfunction "GND_21") (pintype "passive"))
      (node (ref "IC19") (pin "7") (pinfunction "OEB_7") (pintype "passive"))
      (node (ref "J15") (pin "2") (pinfunction "Y_2") (pintype "passive"))
      (node (ref "J16") (pin "2") (pinfunction "Y_2") (pintype "passive"))
      (node (ref "R111") (pin "1") (pinfunction "1_1") (pintype "passive"))
      (node (ref "R123") (pin "1") (pinfunction "1_1") (pintype "passive"))
      (node (ref "R128") (pin "2") (pinfunction "2_2") (pintype "passive"))
      (node (ref "R130") (pin "1") (pinfunction "1_1") (pintype "passive"))
      (node (ref "R131") (pin "2") (pinfunction "2_2") (pintype "passive"))
      (node (ref "R132") (pin "2") (pinfunction "2_2") (pintype "passive"))
      (node (ref "R133") (pin "1") (pinfunction "1_1") (pintype "passive"))
      (node (ref "R134") (pin "1") (pinfunction "1_1") (pintype "passive"))
      (node (ref "XO1") (pin "2") (pinfunction "GND_2") (pintype "passive"))
      (node (ref "XO2") (pin "2") (pinfunction "GND_2") (pintype "passive"))
      (node (ref "XO3") (pin "4") (pinfunction "GND_4") (pintype "passive"))
      (node (ref "XT1") (pin "2") (pinfunction "GND_2") (pintype "passive"))
      (node (ref "XT1") (pin "4") (pinfunction "GND_4") (pintype "passive"))
    )
    (net (code "28") (name "Net-(C312-Pad1)") (class "Default")
      (node (ref "C312") (pin "1") (pinfunction "1_1") (pintype "passive"))
      (node (ref "C313") (pin "2") (pinfunction "2_2") (pintype "passive"))
      (node (ref "R111") (pin "2") (pinfunction "2_2") (pintype "passive"))
    )
    (net (code "29") (name "Net-(C312-Pad2)") (class "Default")
      (node (ref "C312") (pin "2") (pinfunction "2_2") (pintype "passive"))
      (node (ref "R107") (pin "1") (pinfunction "1_1") (pintype "passive"))
      (node (ref "R109") (pin "2") (pinfunction "2_2") (pintype "passive"))
      (node (ref "R112") (pin "1") (pinfunction "1_1") (pintype "passive"))
      (node (ref "R114") (pin "1") (pinfunction "1_1") (pintype "passive"))
      (node (ref "R116") (pin "1") (pinfunction "1_1") (pintype "passive"))
    )
    (net (code "30") (name "Net-(C334-Pad2)") (class "Default")
      (node (ref "C334") (pin "2") (pinfunction "2_2") (pintype "passive"))
      (node (ref "FR44") (pin "2") (pinfunction "2_2") (pintype "passive"))
      (node (ref "R121") (pin "2") (pinfunction "2_2") (pintype "passive"))
    )
    (net (code "31") (name "Net-(C336-Pad2)") (class "Default")
      (node (ref "C336") (pin "2") (pinfunction "2_2") (pintype "passive"))
      (node (ref "C337") (pin "1") (pinfunction "1_1") (pintype "passive"))
      (node (ref "R123") (pin "2") (pinfunction "2_2") (pintype "passive"))
    )
    (net (code "32") (name "Net-(C339-Pad2)") (class "Default")
      (node (ref "C339") (pin "2") (pinfunction "2_2") (pintype "passive"))
      (node (ref "C340") (pin "1") (pinfunction "1_1") (pintype "passive"))
      (node (ref "C341") (pin "1") (pinfunction "1_1") (pintype "passive"))
      (node (ref "FR46") (pin "2") (pinfunction "2_2") (pintype "passive"))
      (node (ref "IC18") (pin "6") (pinfunction "AVdd_6") (pintype "passive"))
      (node (ref "IC18") (pin "7") (pinfunction "AVdd_7") (pintype "passive"))
    )
    (net (code "33") (name "Net-(C346-Pad1)") (class "Default")
      (node (ref "C346") (pin "1") (pinfunction "1_1") (pintype "passive"))
      (node (ref "C347") (pin "2") (pinfunction "2_2") (pintype "passive"))
      (node (ref "R130") (pin "2") (pinfunction "2_2") (pintype "passive"))
    )
    (net (code "34") (name "Net-(C348-Pad2)") (class "Default")
      (node (ref "C348") (pin "2") (pinfunction "2_2") (pintype "passive"))
      (node (ref "R127") (pin "2") (pinfunction "2_2") (pintype "passive"))
      (node (ref "R129") (pin "1") (pinfunction "1_1") (pintype "passive"))
    )
    (net (code "35") (name "Net-(C349-Pad1)") (class "Default")
      (node (ref "C349") (pin "1") (pinfunction "1_1") (pintype "passive"))
      (node (ref "R134") (pin "2") (pinfunction "2_2") (pintype "passive"))
    )
    (net (code "36") (name "Net-(FR40-Pad2)") (class "Default")
      (node (ref "FR40") (pin "2") (pinfunction "2_2") (pintype "passive"))
      (node (ref "R115") (pin "2") (pinfunction "2_2") (pintype "passive"))
      (node (ref "R117") (pin "1") (pinfunction "1_1") (pintype "passive"))
    )
    (net (code "37") (name "Net-(IC16-CLKin)") (class "Default")
      (node (ref "C313") (pin "1") (pinfunction "1_1") (pintype "passive"))
      (node (ref "IC16") (pin "21") (pinfunction "CLKin_21") (pintype "passive"))
    )
    (net (code "38") (name "Net-(IC16-CLKin*)") (class "Default")
      (node (ref "C314") (pin "2") (pinfunction "2_2") (pintype "passive"))
      (node (ref "IC16") (pin "20") (pinfunction "CLKin*_20") (pintype "passive"))
    )
    (net (code "39") (name "Net-(IC16-CLKout0)") (class "Default")
      (node (ref "IC16") (pin "3") (pinfunction "CLKout0_3") (pintype "passive"))
      (node (ref "R110") (pin "2") (pinfunction "2_2") (pintype "passive"))
    )
    (net (code "40") (name "Net-(IC16-CLKout1)") (class "Default")
      (node (ref "IC16") (pin "5") (pinfunction "CLKout1_5") (pintype "passive"))
      (node (ref "R113") (pin "2") (pinfunction "2_2") (pintype "passive"))
    )
    (net (code "41") (name "Net-(IC16-OE)") (class "Default")
      (node (ref "IC16") (pin "24") (pinfunction "OE_24") (pintype "passive"))
      (node (ref "R106") (pin "1") (pinfunction "1_1") (pintype "passive"))
    )
    (net (code "42") (name "Net-(IC17-VDD)") (class "Default")
      (node (ref "C335") (pin "1") (pinfunction "1_1") (pintype "passive"))
      (node (ref "FR45") (pin "2") (pinfunction "2_2") (pintype "passive"))
      (node (ref "IC17") (pin "4") (pinfunction "VDD_4") (pintype "power_in"))
    )
    (net (code "43") (name "Net-(IC17-VOUT)") (class "Default")
      (node (ref "FR44") (pin "1") (pinfunction "1_1") (pintype "passive"))
      (node (ref "IC17") (pin "6") (pinfunction "VOUT_6") (pintype "tri_state"))
    )
    (net (code "44") (name "Net-(IC18-CE)") (class "Default")
      (node (ref "IC18") (pin "11") (pinfunction "CE_11") (pintype "passive"))
      (node (ref "R125") (pin "1") (pinfunction "1_1") (pintype "passive"))
    )
    (net (code "45") (name "Net-(IC18-CLK)") (class "Default")
      (node (ref "C352") (pin "2") (pinfunction "2_2") (pintype "passive"))
      (node (ref "IC18") (pin "12") (pinfunction "CLK_12") (pintype "passive"))
      (node (ref "R135") (pin "2") (pinfunction "2_2") (pintype "passive"))
    )
    (net (code "46") (name "Net-(IC18-CP)") (class "Default")
      (node (ref "C349") (pin "2") (pinfunction "2_2") (pintype "passive"))
      (node (ref "C350") (pin "2") (pinfunction "2_2") (pintype "passive"))
      (node (ref "IC18") (pin "20") (pinfunction "CP_20") (pintype "passive"))
      (node (ref "R127") (pin "1") (pinfunction "1_1") (pintype "passive"))
    )
    (net (code "47") (name "Net-(IC18-DATA)") (class "Default")
      (node (ref "IC18") (pin "13") (pinfunction "DATA_13") (pintype "passive"))
      (node (ref "R136") (pin "2") (pinfunction "2_2") (pintype "passive"))
    )
    (net (code "48") (name "Net-(IC18-LE)") (class "Default")
      (node (ref "IC18") (pin "14") (pinfunction "LE_14") (pintype "passive"))
      (node (ref "R137") (pin "2") (pinfunction "2_2") (pintype "passive"))
    )
    (net (code "49") (name "Net-(IC18-REFin)") (class "Default")
      (node (ref "C346") (pin "2") (pinfunction "2_2") (pintype "passive"))
      (node (ref "IC18") (pin "8") (pinfunction "REFin_8") (pintype "passive"))
    )
    (net (code "50") (name "Net-(IC18-RFinA)") (class "Default")
      (node (ref "C336") (pin "1") (pinfunction "1_1") (pintype "passive"))
      (node (ref "IC18") (pin "5") (pinfunction "RFinA_5") (pintype "passive"))
    )
    (net (code "51") (name "Net-(IC18-RFinB)") (class "Default")
      (node (ref "C351") (pin "1") (pinfunction "1_1") (pintype "passive"))
      (node (ref "IC18") (pin "4") (pinfunction "RFinB_4") (pintype "passive"))
    )
    (net (code "52") (name "Net-(IC18-Rset)") (class "Default")
      (node (ref "IC18") (pin "19") (pinfunction "Rset_19") (pintype "passive"))
      (node (ref "R132") (pin "1") (pinfunction "1_1") (pintype "passive"))
    )
    (net (code "53") (name "Net-(IC18-Vp)") (class "Default")
      (node (ref "C344") (pin "2") (pinfunction "2_2") (pintype "passive"))
      (node (ref "C345") (pin "1") (pinfunction "1_1") (pintype "passive"))
      (node (ref "IC18") (pin "18") (pinfunction "Vp_18") (pintype "passive"))
      (node (ref "R124") (pin "1") (pinfunction "1_1") (pintype "passive"))
    )
    (net (code "54") (name "Net-(IC19-CLKIN)") (class "Default")
      (node (ref "IC19") (pin "6") (pinfunction "CLKIN_6") (pintype "passive"))
      (node (ref "R126") (pin "2") (pinfunction "2_2") (pintype "passive"))
      (node (ref "R128") (pin "1") (pinfunction "1_1") (pintype "passive"))
    )
    (net (code "55") (name "Net-(IC19-INTR)") (class "Default")
      (node (ref "IC19") (pin "3") (pinfunction "INTR_3") (pintype "passive"))
      (node (ref "R133") (pin "2") (pinfunction "2_2") (pintype "passive"))
    )
    (net (code "56") (name "Net-(J15-X)") (class "Default")
      (node (ref "J15") (pin "1") (pinfunction "X_1") (pintype "passive"))
      (node (ref "R122") (pin "1") (pinfunction "1_1") (pintype "passive"))
    )
    (net (code "57") (name "Net-(R117-Pad2)") (class "Default")
      (node (ref "R117") (pin "2") (pinfunction "2_2") (pintype "passive"))
      (node (ref "R119") (pin "1") (pinfunction "1_1") (pintype "passive"))
    )
    (net (code "58") (name "Net-(XO1-OUT)") (class "Default")
      (node (ref "R107") (pin "2") (pinfunction "2_2") (pintype "passive"))
      (node (ref "XO1") (pin "4") (pinfunction "OUT_4") (pintype "passive"))
      (node (ref "XO2") (pin "3") (pinfunction "OUT_3") (pintype "passive"))
    )
    (net (code "59") (name "Net-(XO1-TRI-ST.)") (class "Default")
      (node (ref "R108") (pin "1") (pinfunction "1_1") (pintype "passive"))
      (node (ref "XO1") (pin "6") (pinfunction "TRI-ST._6") (pintype "passive"))
    )
    (net (code "60") (name "Net-(XO1-VDD)") (class "Default")
      (node (ref "C317") (pin "2") (pinfunction "2_2") (pintype "passive"))
      (node (ref "C318") (pin "2") (pinfunction "2_2") (pintype "passive"))
      (node (ref "R108") (pin "2") (pinfunction "2_2") (pintype "passive"))
      (node (ref "R115") (pin "1") (pinfunction "1_1") (pintype "passive"))
      (node (ref "XO1") (pin "5") (pinfunction "VDD_5") (pintype "passive"))
      (node (ref "XO2") (pin "4") (pinfunction "VDD_4") (pintype "passive"))
    )
    (net (code "61") (name "Net-(XO3-RF_OUT)") (class "Default")
      (node (ref "R116") (pin "2") (pinfunction "2_2") (pintype "passive"))
      (node (ref "XO3") (pin "6") (pinfunction "RF_OUT_6") (pintype "output"))
    )
    (net (code "62") (name "Net-(XO3-VCC)") (class "Default")
      (node (ref "C323") (pin "2") (pinfunction "2_2") (pintype "passive"))
      (node (ref "C324") (pin "2") (pinfunction "2_2") (pintype "passive"))
      (node (ref "R119") (pin "2") (pinfunction "2_2") (pintype "passive"))
      (node (ref "XO3") (pin "9") (pinfunction "VCC_9") (pintype "power_in"))
    )
    (net (code "63") (name "Net-(XO3-VCO)") (class "Default")
      (node (ref "R118") (pin "2") (pinfunction "2_2") (pintype "passive"))
      (node (ref "XO3") (pin "1") (pinfunction "VCO_1") (pintype "input"))
    )
    (net (code "64") (name "Net-(XO3-VC_FILTER)") (class "Default")
      (node (ref "C325") (pin "2") (pinfunction "2_2") (pintype "passive"))
      (node (ref "XO3") (pin "7") (pinfunction "VC_FILTER_7") (pintype "input"))
    )
    (net (code "65") (name "VCC1P8") (class "Default")
      (node (ref "C354") (pin "1") (pinfunction "1_1") (pintype "passive"))
      (node (ref "FR42") (pin "1") (pinfunction "1_1") (pintype "passive"))
      (node (ref "IC19") (pin "14") (pinfunction "VDDOD_14") (pintype "passive"))
    )
    (net (code "66") (name "VCC3P3_CLK") (class "Default")
      (node (ref "C338") (pin "2") (pinfunction "2_2") (pintype "passive"))
      (node (ref "C342") (pin "1") (pinfunction "1_1") (pintype "passive"))
      (node (ref "C343") (pin "1") (pinfunction "1_1") (pintype "passive"))
      (node (ref "C357") (pin "1") (pinfunction "1_1") (pintype "passive"))
      (node (ref "C358") (pin "1") (pinfunction "1_1") (pintype "passive"))
      (node (ref "C359") (pin "1") (pinfunction "1_1") (pintype "passive"))
      (node (ref "FR40") (pin "1") (pinfunction "1_1") (pintype "passive"))
      (node (ref "FR41") (pin "1") (pinfunction "1_1") (pintype "passive"))
      (node (ref "FR43") (pin "1") (pinfunction "1_1") (pintype "passive"))
      (node (ref "FR45") (pin "1") (pinfunction "1_1") (pintype "passive"))
      (node (ref "FR46") (pin "1") (pinfunction "1_1") (pintype "passive"))
      (node (ref "IC18") (pin "16") (pinfunction "DVdd_16") (pintype "passive"))
      (node (ref "IC18") (pin "17") (pinfunction "DVdd_17") (pintype "passive"))
      (node (ref "IC19") (pin "11") (pinfunction "VDDOA_11") (pintype "passive"))
      (node (ref "IC19") (pin "18") (pinfunction "VDDOC_18") (pintype "passive"))
      (node (ref "IC19") (pin "20") (pinfunction "VDD_20") (pintype "passive"))
      (node (ref "R124") (pin "2") (pinfunction "2_2") (pintype "passive"))
      (node (ref "R125") (pin "2") (pinfunction "2_2") (pintype "passive"))
    )
    (net (code "67") (name "VCC3P3_LMK") (class "Default")
      (node (ref "C319") (pin "2") (pinfunction "2_2") (pintype "passive"))
      (node (ref "C320") (pin "2") (pinfunction "2_2") (pintype "passive"))
      (node (ref "C321") (pin "2") (pinfunction "2_2") (pintype "passive"))
      (node (ref "C322") (pin "2") (pinfunction "2_2") (pintype "passive"))
      (node (ref "FR41") (pin "2") (pinfunction "2_2") (pintype "passive"))
      (node (ref "IC16") (pin "23") (pinfunction "Vdd_23") (pintype "passive"))
      (node (ref "IC16") (pin "8") (pinfunction "Vdd_8") (pintype "passive"))
      (node (ref "R106") (pin "2") (pinfunction "2_2") (pintype "passive"))
      (node (ref "R120") (pin "1") (pinfunction "1_1") (pintype "passive"))
    )
    (net (code "68") (name "VDIO_LMK") (class "Default")
      (node (ref "C330") (pin "2") (pinfunction "2_2") (pintype "passive"))
      (node (ref "C331") (pin "2") (pinfunction "2_2") (pintype "passive"))
      (node (ref "C332") (pin "2") (pinfunction "2_2") (pintype "passive"))
      (node (ref "C333") (pin "2") (pinfunction "2_2") (pintype "passive"))
      (node (ref "FR43") (pin "2") (pinfunction "2_2") (pintype "passive"))
      (node (ref "IC16") (pin "14") (pinfunction "Vddo_14") (pintype "passive"))
      (node (ref "IC16") (pin "18") (pinfunction "Vddo_18") (pintype "passive"))
    )
    (net (code "69") (name "VDIO_LMS_FPGA") (class "Default")
      (node (ref "C353") (pin "1") (pinfunction "1_1") (pintype "passive"))
      (node (ref "IC19") (pin "10") (pinfunction "VDDOB_10") (pintype "passive"))
      (node (ref "R120") (pin "2") (pinfunction "2_2") (pintype "passive"))
    )
    (net (code "70") (name "unconnected-(IC16-OSCin-Pad9)") (class "Default")
      (node (ref "IC16") (pin "9") (pinfunction "OSCin_9") (pintype "passive+no_connect"))
    )
    (net (code "71") (name "unconnected-(IC16-OSCout-Pad10)") (class "Default")
      (node (ref "IC16") (pin "10") (pinfunction "OSCout_10") (pintype "passive+no_connect"))
    )
    (net (code "72") (name "unconnected-(XO1-T.S.-Pad3)") (class "Default")
      (node (ref "XO1") (pin "3") (pinfunction "T.S._3") (pintype "passive+no_connect"))
    )
    (net (code "73") (name "unconnected-(XO3-NC-Pad2)") (class "Default")
      (node (ref "XO3") (pin "2") (pinfunction "NC_2") (pintype "passive+no_connect"))
    )
    (net (code "74") (name "unconnected-(XO3-NC-Pad3)") (class "Default")
      (node (ref "XO3") (pin "3") (pinfunction "NC_3") (pintype "passive+no_connect"))
    )
    (net (code "75") (name "unconnected-(XO3-NC-Pad5)") (class "Default")
      (node (ref "XO3") (pin "5") (pinfunction "NC_5") (pintype "passive+no_connect"))
    )
    (net (code "76") (name "unconnected-(XO3-NC-Pad8)") (class "Default")
      (node (ref "XO3") (pin "8") (pinfunction "NC_8") (pintype "passive+no_connect"))
    )
    (net (code "77") (name "unconnected-(XO3-NC-Pad10)") (class "Default")
      (node (ref "XO3") (pin "10") (pinfunction "NC_10") (pintype "passive+no_connect"))
    )
  )
)
